# MIDI_CV_CONV.net
KiCad netlist of a schematic drawn in EAGLE
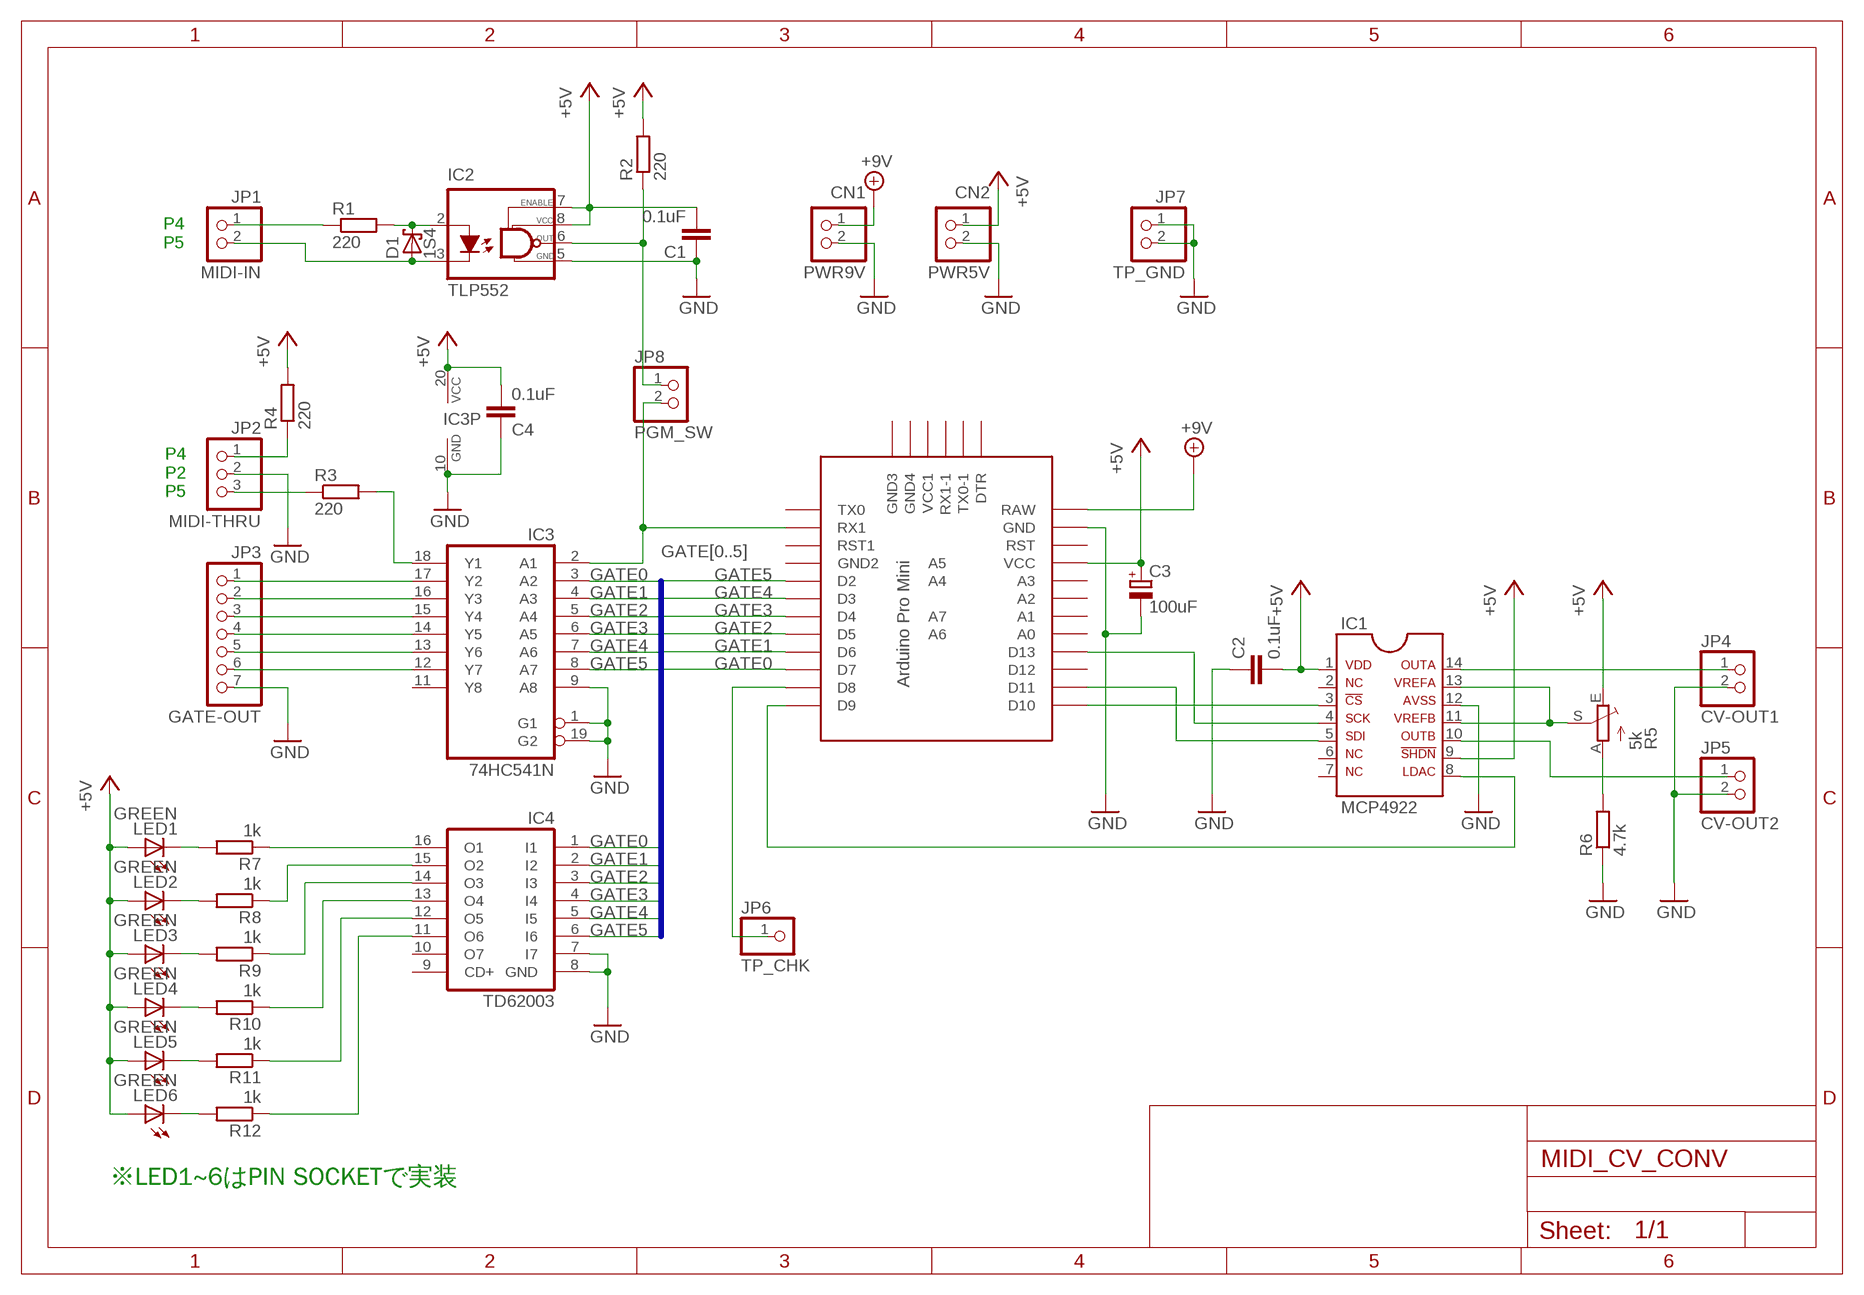
[diagram p0: schematic, sheet 1]

(export (version "E")
  (design (tool "Eeschema 10.0.6"))
  (components
    (comp (ref "C1")
      (value "0.1uF")
      (footprint "eagle-import:C025-024X044")
      (libsource (lib "eagle-import") (part "C-EU025-024X044"))
    )
    (comp (ref "C2")
      (value "0.1uF")
      (footprint "eagle-import:C050-024X044")
      (libsource (lib "eagle-import") (part "C-EU050-024X044"))
    )
    (comp (ref "C3")
      (value "100uF")
      (footprint "eagle-import:E2,5-7")
      (libsource (lib "eagle-import") (part "CPOL-EUE2.5-7"))
    )
    (comp (ref "C4")
      (value "0.1uF")
      (footprint "eagle-import:C025-024X044")
      (libsource (lib "eagle-import") (part "C-EU025-024X044"))
    )
    (comp (ref "CN1")
      (value "PWR9V")
      (footprint "eagle-import:B2B-XH-A")
      (libsource (lib "eagle-import") (part "B2B-XH-A"))
    )
    (comp (ref "CN2")
      (value "PWR5V")
      (footprint "eagle-import:B2B-XH-A")
      (libsource (lib "eagle-import") (part "B2B-XH-A"))
    )
    (comp (ref "D1")
      (value "1S4")
      (footprint "eagle-import:DO35-7")
      (libsource (lib "eagle-import") (part "SCHOTTKY-DIODEDO35-7"))
    )
    (comp (ref "IC1")
      (value "MCP4922")
      (footprint "eagle-import:MCP4922")
      (libsource (lib "eagle-import") (part "MCP4922"))
    )
    (comp (ref "IC2")
      (value "TLP552")
      (footprint "eagle-import:DIL8")
      (libsource (lib "eagle-import") (part "TLP552"))
    )
    (comp (ref "IC3")
      (value "74HC541N")
      (footprint "eagle-import:DIL20")
      (libsource (lib "eagle-import") (part "74541NHC"))
    )
    (comp (ref "IC4")
      (value "TD62003")
      (footprint "eagle-import:DIL16")
      (libsource (lib "eagle-import") (part "ULN2001AN"))
    )
    (comp (ref "JP1")
      (value "MIDI-IN")
      (footprint "eagle-import:1X02")
      (libsource (lib "eagle-import") (part "PINHD-1X2"))
    )
    (comp (ref "JP2")
      (value "MIDI-THRU")
      (footprint "eagle-import:1X03")
      (libsource (lib "eagle-import") (part "PINHD-1X3"))
    )
    (comp (ref "JP3")
      (value "GATE-OUT")
      (footprint "eagle-import:1X07")
      (libsource (lib "eagle-import") (part "PINHD-1X7"))
    )
    (comp (ref "JP4")
      (value "CV-OUT1")
      (footprint "eagle-import:1X02")
      (libsource (lib "eagle-import") (part "PINHD-1X2"))
    )
    (comp (ref "JP5")
      (value "CV-OUT2")
      (footprint "eagle-import:1X02")
      (libsource (lib "eagle-import") (part "PINHD-1X2"))
    )
    (comp (ref "JP6")
      (value "TP_CHK")
      (footprint "eagle-import:1X01")
      (libsource (lib "eagle-import") (part "PINHD-1X1"))
    )
    (comp (ref "JP7")
      (value "TP_GND")
      (footprint "eagle-import:1X02")
      (libsource (lib "eagle-import") (part "PINHD-1X2"))
    )
    (comp (ref "JP8")
      (value "PGM_SW")
      (footprint "eagle-import:1X02")
      (libsource (lib "eagle-import") (part "PINHD-1X2"))
    )
    (comp (ref "LED1")
      (value "GREEN")
      (footprint "eagle-import:LED3MM")
      (libsource (lib "eagle-import") (part "LED3MM"))
    )
    (comp (ref "LED2")
      (value "GREEN")
      (footprint "eagle-import:LED3MM")
      (libsource (lib "eagle-import") (part "LED3MM"))
    )
    (comp (ref "LED3")
      (value "GREEN")
      (footprint "eagle-import:LED3MM")
      (libsource (lib "eagle-import") (part "LED3MM"))
    )
    (comp (ref "LED4")
      (value "GREEN")
      (footprint "eagle-import:LED3MM")
      (libsource (lib "eagle-import") (part "LED3MM"))
    )
    (comp (ref "LED5")
      (value "GREEN")
      (footprint "eagle-import:LED3MM")
      (libsource (lib "eagle-import") (part "LED3MM"))
    )
    (comp (ref "LED6")
      (value "GREEN")
      (footprint "eagle-import:LED3MM")
      (libsource (lib "eagle-import") (part "LED3MM"))
    )
    (comp (ref "R1")
      (value "220")
      (footprint "eagle-import:0207_7")
      (libsource (lib "eagle-import") (part "R-EU_0207/7"))
    )
    (comp (ref "R2")
      (value "220")
      (footprint "eagle-import:0207_7")
      (libsource (lib "eagle-import") (part "R-EU_0207/7"))
    )
    (comp (ref "R3")
      (value "220")
      (footprint "eagle-import:0207_7")
      (libsource (lib "eagle-import") (part "R-EU_0207/7"))
    )
    (comp (ref "R4")
      (value "220")
      (footprint "eagle-import:0207_7")
      (libsource (lib "eagle-import") (part "R-EU_0207/7"))
    )
    (comp (ref "R5")
      (value "5k")
      (footprint "eagle-import:CT6")
      (libsource (lib "eagle-import") (part "TRIM_EU-CT6"))
    )
    (comp (ref "R6")
      (value "4.7k")
      (footprint "eagle-import:0207_7")
      (libsource (lib "eagle-import") (part "R-EU_0207/7"))
    )
    (comp (ref "R7")
      (value "1k")
      (footprint "eagle-import:0207_2V")
      (libsource (lib "eagle-import") (part "R-EU_0207/2V"))
    )
    (comp (ref "R8")
      (value "1k")
      (footprint "eagle-import:0207_2V")
      (libsource (lib "eagle-import") (part "R-EU_0207/2V"))
    )
    (comp (ref "R9")
      (value "1k")
      (footprint "eagle-import:0207_2V")
      (libsource (lib "eagle-import") (part "R-EU_0207/2V"))
    )
    (comp (ref "R10")
      (value "1k")
      (footprint "eagle-import:0207_2V")
      (libsource (lib "eagle-import") (part "R-EU_0207/2V"))
    )
    (comp (ref "R11")
      (value "1k")
      (footprint "eagle-import:0207_2V")
      (libsource (lib "eagle-import") (part "R-EU_0207/2V"))
    )
    (comp (ref "R12")
      (value "1k")
      (footprint "eagle-import:0207_2V")
      (libsource (lib "eagle-import") (part "R-EU_0207/2V"))
    )
    (comp (ref "U$1")
      (value "PRO-MINI-2 (16MHz/5V)")
      (footprint "eagle-import:PRO-MINI-2")
      (libsource (lib "eagle-import") (part "PRO-MINI-2"))
    )
  )
  (nets
    (net (code "1") (name "+5V") (class "Default")
      (node (ref "C1") (pin "2") (pinfunction "2_2") (pintype "passive"))
      (node (ref "C2") (pin "2") (pinfunction "2_2") (pintype "passive"))
      (node (ref "C3") (pin "+") (pinfunction "+_+") (pintype "passive"))
      (node (ref "C4") (pin "2") (pinfunction "2_2") (pintype "passive"))
      (node (ref "CN2") (pin "1") (pinfunction "1_1") (pintype "passive"))
      (node (ref "IC1") (pin "1") (pinfunction "1_1") (pintype "power_in"))
      (node (ref "IC1") (pin "9") (pinfunction "9_9") (pintype "input"))
      (node (ref "IC2") (pin "7") (pinfunction "EN_7") (pintype "input"))
      (node (ref "IC2") (pin "8") (pinfunction "VCC_8") (pintype "power_in"))
      (node (ref "IC3") (pin "20") (pinfunction "VCC_20") (pintype "power_in"))
      (node (ref "LED1") (pin "A") (pinfunction "A_A") (pintype "passive"))
      (node (ref "LED2") (pin "A") (pinfunction "A_A") (pintype "passive"))
      (node (ref "LED3") (pin "A") (pinfunction "A_A") (pintype "passive"))
      (node (ref "LED4") (pin "A") (pinfunction "A_A") (pintype "passive"))
      (node (ref "LED5") (pin "A") (pinfunction "A_A") (pintype "passive"))
      (node (ref "LED6") (pin "A") (pinfunction "A_A") (pintype "passive"))
      (node (ref "R2") (pin "2") (pinfunction "2_2") (pintype "passive"))
      (node (ref "R4") (pin "2") (pinfunction "2_2") (pintype "passive"))
      (node (ref "R5") (pin "E") (pinfunction "E_E") (pintype "passive"))
      (node (ref "U$1") (pin "VCC") (pinfunction "VCC_VCC") (pintype "bidirectional"))
    )
    (net (code "2") (name "+9V") (class "Default")
      (node (ref "CN1") (pin "1") (pinfunction "1_1") (pintype "passive"))
      (node (ref "U$1") (pin "RAW") (pinfunction "RAW_RAW") (pintype "bidirectional"))
    )
    (net (code "3") (name "/GATE0") (class "Default")
      (node (ref "IC3") (pin "3") (pinfunction "A2_3") (pintype "input"))
      (node (ref "IC4") (pin "1") (pinfunction "I1_1") (pintype "input"))
      (node (ref "U$1") (pin "D7") (pinfunction "D7_D7") (pintype "bidirectional"))
    )
    (net (code "4") (name "/GATE1") (class "Default")
      (node (ref "IC3") (pin "4") (pinfunction "A3_4") (pintype "input"))
      (node (ref "IC4") (pin "2") (pinfunction "I2_2") (pintype "input"))
      (node (ref "U$1") (pin "D6") (pinfunction "D6_D6") (pintype "bidirectional"))
    )
    (net (code "5") (name "/GATE2") (class "Default")
      (node (ref "IC3") (pin "5") (pinfunction "A4_5") (pintype "input"))
      (node (ref "IC4") (pin "3") (pinfunction "I3_3") (pintype "input"))
      (node (ref "U$1") (pin "D5") (pinfunction "D5_D5") (pintype "bidirectional"))
    )
    (net (code "6") (name "/GATE3") (class "Default")
      (node (ref "IC3") (pin "6") (pinfunction "A5_6") (pintype "input"))
      (node (ref "IC4") (pin "4") (pinfunction "I4_4") (pintype "input"))
      (node (ref "U$1") (pin "D4") (pinfunction "D4_D4") (pintype "bidirectional"))
    )
    (net (code "7") (name "/GATE4") (class "Default")
      (node (ref "IC3") (pin "7") (pinfunction "A6_7") (pintype "input"))
      (node (ref "IC4") (pin "5") (pinfunction "I5_5") (pintype "input"))
      (node (ref "U$1") (pin "D3") (pinfunction "D3_D3") (pintype "bidirectional"))
    )
    (net (code "8") (name "/GATE5") (class "Default")
      (node (ref "IC3") (pin "8") (pinfunction "A7_8") (pintype "input"))
      (node (ref "IC4") (pin "6") (pinfunction "I6_6") (pintype "input"))
      (node (ref "U$1") (pin "D2") (pinfunction "D2_D2") (pintype "bidirectional"))
    )
    (net (code "9") (name "GND") (class "Default")
      (node (ref "C1") (pin "1") (pinfunction "1_1") (pintype "passive"))
      (node (ref "C2") (pin "1") (pinfunction "1_1") (pintype "passive"))
      (node (ref "C3") (pin "-") (pinfunction "-_-") (pintype "passive"))
      (node (ref "C4") (pin "1") (pinfunction "1_1") (pintype "passive"))
      (node (ref "CN1") (pin "2") (pinfunction "2_2") (pintype "passive"))
      (node (ref "CN2") (pin "2") (pinfunction "2_2") (pintype "passive"))
      (node (ref "IC1") (pin "12") (pinfunction "12_12") (pintype "power_in"))
      (node (ref "IC2") (pin "5") (pinfunction "GND_5") (pintype "power_in"))
      (node (ref "IC3") (pin "1") (pinfunction "G1_1") (pintype "input"))
      (node (ref "IC3") (pin "10") (pinfunction "GND_10") (pintype "power_in"))
      (node (ref "IC3") (pin "19") (pinfunction "G2_19") (pintype "input"))
      (node (ref "IC3") (pin "9") (pinfunction "A8_9") (pintype "input"))
      (node (ref "IC4") (pin "7") (pinfunction "I7_7") (pintype "input"))
      (node (ref "IC4") (pin "8") (pinfunction "GND_8") (pintype "power_in"))
      (node (ref "JP2") (pin "2") (pinfunction "2_2") (pintype "passive"))
      (node (ref "JP3") (pin "7") (pinfunction "7_7") (pintype "passive"))
      (node (ref "JP4") (pin "2") (pinfunction "2_2") (pintype "passive"))
      (node (ref "JP5") (pin "2") (pinfunction "2_2") (pintype "passive"))
      (node (ref "JP7") (pin "1") (pinfunction "1_1") (pintype "passive"))
      (node (ref "JP7") (pin "2") (pinfunction "2_2") (pintype "passive"))
      (node (ref "R6") (pin "1") (pinfunction "1_1") (pintype "passive"))
      (node (ref "U$1") (pin "GND") (pinfunction "GND_GND") (pintype "bidirectional"))
    )
    (net (code "10") (name "Net-(IC1-Pad3)") (class "Default")
      (node (ref "IC1") (pin "3") (pinfunction "3_3") (pintype "input"))
      (node (ref "U$1") (pin "D10") (pinfunction "D10_D10") (pintype "bidirectional"))
    )
    (net (code "11") (name "Net-(IC1-Pad4)") (class "Default")
      (node (ref "IC1") (pin "4") (pinfunction "4_4") (pintype "input"))
      (node (ref "U$1") (pin "D13") (pinfunction "D13_D13") (pintype "bidirectional"))
    )
    (net (code "12") (name "Net-(IC1-Pad5)") (class "Default")
      (node (ref "IC1") (pin "5") (pinfunction "5_5") (pintype "input"))
      (node (ref "U$1") (pin "D11") (pinfunction "D11_D11") (pintype "bidirectional"))
    )
    (net (code "13") (name "Net-(IC1-Pad8)") (class "Default")
      (node (ref "IC1") (pin "8") (pinfunction "8_8") (pintype "input"))
      (node (ref "U$1") (pin "D9") (pinfunction "D9_D9") (pintype "bidirectional"))
    )
    (net (code "14") (name "Net-(IC1-Pad10)") (class "Default")
      (node (ref "IC1") (pin "10") (pinfunction "10_10") (pintype "output"))
      (node (ref "JP5") (pin "1") (pinfunction "1_1") (pintype "passive"))
    )
    (net (code "15") (name "Net-(IC1-Pad11)") (class "Default")
      (node (ref "IC1") (pin "11") (pinfunction "11_11") (pintype "input"))
      (node (ref "IC1") (pin "13") (pinfunction "13_13") (pintype "input"))
      (node (ref "R5") (pin "S") (pinfunction "S_S") (pintype "passive"))
    )
    (net (code "16") (name "Net-(IC1-Pad14)") (class "Default")
      (node (ref "IC1") (pin "14") (pinfunction "14_14") (pintype "output"))
      (node (ref "JP4") (pin "1") (pinfunction "1_1") (pintype "passive"))
    )
    (net (code "17") (name "Net-(IC2-A)") (class "Default")
      (node (ref "D1") (pin "C") (pinfunction "C_C") (pintype "passive"))
      (node (ref "IC2") (pin "2") (pinfunction "A_2") (pintype "passive"))
      (node (ref "R1") (pin "2") (pinfunction "2_2") (pintype "passive"))
    )
    (net (code "18") (name "Net-(IC2-C)") (class "Default")
      (node (ref "D1") (pin "A") (pinfunction "A_A") (pintype "passive"))
      (node (ref "IC2") (pin "3") (pinfunction "C_3") (pintype "passive"))
      (node (ref "JP1") (pin "2") (pinfunction "2_2") (pintype "passive"))
    )
    (net (code "19") (name "Net-(IC2-OUT)") (class "Default")
      (node (ref "IC2") (pin "6") (pinfunction "OUT_6") (pintype "output"))
      (node (ref "JP8") (pin "1") (pinfunction "1_1") (pintype "passive"))
      (node (ref "R2") (pin "1") (pinfunction "1_1") (pintype "passive"))
    )
    (net (code "20") (name "Net-(IC3A-A1)") (class "Default")
      (node (ref "IC3") (pin "2") (pinfunction "A1_2") (pintype "input"))
      (node (ref "JP8") (pin "2") (pinfunction "2_2") (pintype "passive"))
      (node (ref "U$1") (pin "RX1") (pinfunction "RX1_RX1") (pintype "bidirectional"))
    )
    (net (code "21") (name "Net-(IC3A-Y1)") (class "Default")
      (node (ref "IC3") (pin "18") (pinfunction "Y1_18") (pintype "tri_state"))
      (node (ref "R3") (pin "2") (pinfunction "2_2") (pintype "passive"))
    )
    (net (code "22") (name "Net-(IC3A-Y2)") (class "Default")
      (node (ref "IC3") (pin "17") (pinfunction "Y2_17") (pintype "tri_state"))
      (node (ref "JP3") (pin "1") (pinfunction "1_1") (pintype "passive"))
    )
    (net (code "23") (name "Net-(IC3A-Y3)") (class "Default")
      (node (ref "IC3") (pin "16") (pinfunction "Y3_16") (pintype "tri_state"))
      (node (ref "JP3") (pin "2") (pinfunction "2_2") (pintype "passive"))
    )
    (net (code "24") (name "Net-(IC3A-Y4)") (class "Default")
      (node (ref "IC3") (pin "15") (pinfunction "Y4_15") (pintype "tri_state"))
      (node (ref "JP3") (pin "3") (pinfunction "3_3") (pintype "passive"))
    )
    (net (code "25") (name "Net-(IC3A-Y5)") (class "Default")
      (node (ref "IC3") (pin "14") (pinfunction "Y5_14") (pintype "tri_state"))
      (node (ref "JP3") (pin "4") (pinfunction "4_4") (pintype "passive"))
    )
    (net (code "26") (name "Net-(IC3A-Y6)") (class "Default")
      (node (ref "IC3") (pin "13") (pinfunction "Y6_13") (pintype "tri_state"))
      (node (ref "JP3") (pin "5") (pinfunction "5_5") (pintype "passive"))
    )
    (net (code "27") (name "Net-(IC3A-Y7)") (class "Default")
      (node (ref "IC3") (pin "12") (pinfunction "Y7_12") (pintype "tri_state"))
      (node (ref "JP3") (pin "6") (pinfunction "6_6") (pintype "passive"))
    )
    (net (code "28") (name "Net-(IC4-O1)") (class "Default")
      (node (ref "IC4") (pin "16") (pinfunction "O1_16") (pintype "open_collector"))
      (node (ref "R7") (pin "1") (pinfunction "1_1") (pintype "passive"))
    )
    (net (code "29") (name "Net-(IC4-O2)") (class "Default")
      (node (ref "IC4") (pin "15") (pinfunction "O2_15") (pintype "open_collector"))
      (node (ref "R8") (pin "1") (pinfunction "1_1") (pintype "passive"))
    )
    (net (code "30") (name "Net-(IC4-O3)") (class "Default")
      (node (ref "IC4") (pin "14") (pinfunction "O3_14") (pintype "open_collector"))
      (node (ref "R9") (pin "1") (pinfunction "1_1") (pintype "passive"))
    )
    (net (code "31") (name "Net-(IC4-O4)") (class "Default")
      (node (ref "IC4") (pin "13") (pinfunction "O4_13") (pintype "open_collector"))
      (node (ref "R10") (pin "1") (pinfunction "1_1") (pintype "passive"))
    )
    (net (code "32") (name "Net-(IC4-O5)") (class "Default")
      (node (ref "IC4") (pin "12") (pinfunction "O5_12") (pintype "open_collector"))
      (node (ref "R11") (pin "1") (pinfunction "1_1") (pintype "passive"))
    )
    (net (code "33") (name "Net-(IC4-O6)") (class "Default")
      (node (ref "IC4") (pin "11") (pinfunction "O6_11") (pintype "open_collector"))
      (node (ref "R12") (pin "1") (pinfunction "1_1") (pintype "passive"))
    )
    (net (code "34") (name "Net-(JP1-Pad1)") (class "Default")
      (node (ref "JP1") (pin "1") (pinfunction "1_1") (pintype "passive"))
      (node (ref "R1") (pin "1") (pinfunction "1_1") (pintype "passive"))
    )
    (net (code "35") (name "Net-(JP2-Pad1)") (class "Default")
      (node (ref "JP2") (pin "1") (pinfunction "1_1") (pintype "passive"))
      (node (ref "R4") (pin "1") (pinfunction "1_1") (pintype "passive"))
    )
    (net (code "36") (name "Net-(JP2-Pad3)") (class "Default")
      (node (ref "JP2") (pin "3") (pinfunction "3_3") (pintype "passive"))
      (node (ref "R3") (pin "1") (pinfunction "1_1") (pintype "passive"))
    )
    (net (code "37") (name "Net-(JP6-Pad1)") (class "Default")
      (node (ref "JP6") (pin "1") (pinfunction "1_1") (pintype "passive"))
      (node (ref "U$1") (pin "D8") (pinfunction "D8_D8") (pintype "bidirectional"))
    )
    (net (code "38") (name "Net-(LED1-C)") (class "Default")
      (node (ref "LED1") (pin "K") (pinfunction "C_K") (pintype "passive"))
      (node (ref "R7") (pin "2") (pinfunction "2_2") (pintype "passive"))
    )
    (net (code "39") (name "Net-(LED2-C)") (class "Default")
      (node (ref "LED2") (pin "K") (pinfunction "C_K") (pintype "passive"))
      (node (ref "R8") (pin "2") (pinfunction "2_2") (pintype "passive"))
    )
    (net (code "40") (name "Net-(LED3-C)") (class "Default")
      (node (ref "LED3") (pin "K") (pinfunction "C_K") (pintype "passive"))
      (node (ref "R9") (pin "2") (pinfunction "2_2") (pintype "passive"))
    )
    (net (code "41") (name "Net-(LED4-C)") (class "Default")
      (node (ref "LED4") (pin "K") (pinfunction "C_K") (pintype "passive"))
      (node (ref "R10") (pin "2") (pinfunction "2_2") (pintype "passive"))
    )
    (net (code "42") (name "Net-(LED5-C)") (class "Default")
      (node (ref "LED5") (pin "K") (pinfunction "C_K") (pintype "passive"))
      (node (ref "R11") (pin "2") (pinfunction "2_2") (pintype "passive"))
    )
    (net (code "43") (name "Net-(LED6-C)") (class "Default")
      (node (ref "LED6") (pin "K") (pinfunction "C_K") (pintype "passive"))
      (node (ref "R12") (pin "2") (pinfunction "2_2") (pintype "passive"))
    )
    (net (code "44") (name "Net-(R5-PadA)") (class "Default")
      (node (ref "R5") (pin "A") (pinfunction "A_A") (pintype "passive"))
      (node (ref "R6") (pin "2") (pinfunction "2_2") (pintype "passive"))
    )
    (net (code "45") (name "unconnected-(IC1-Pad2)") (class "Default")
      (node (ref "IC1") (pin "2") (pinfunction "2_2") (pintype "no_connect"))
    )
    (net (code "46") (name "unconnected-(IC1-Pad6)") (class "Default")
      (node (ref "IC1") (pin "6") (pinfunction "6_6") (pintype "no_connect"))
    )
    (net (code "47") (name "unconnected-(IC1-Pad7)") (class "Default")
      (node (ref "IC1") (pin "7") (pinfunction "7_7") (pintype "no_connect"))
    )
    (net (code "48") (name "unconnected-(IC3A-Y8-Pad11)") (class "Default")
      (node (ref "IC3") (pin "11") (pinfunction "Y8_11") (pintype "tri_state"))
    )
    (net (code "49") (name "unconnected-(IC4-CD+-Pad9)") (class "Default")
      (node (ref "IC4") (pin "9") (pinfunction "CD+_9") (pintype "passive"))
    )
    (net (code "50") (name "unconnected-(IC4-O7-Pad10)") (class "Default")
      (node (ref "IC4") (pin "10") (pinfunction "O7_10") (pintype "open_collector"))
    )
    (net (code "51") (name "unconnected-(U$1-GND2-PadGND1)") (class "Default")
      (node (ref "U$1") (pin "GND1") (pinfunction "GND2_GND1") (pintype "bidirectional"))
    )
    (net (code "52") (name "unconnected-(U$1-GND3-PadGND2)") (class "Default")
      (node (ref "U$1") (pin "GND2") (pinfunction "GND3_GND2") (pintype "bidirectional"))
    )
    (net (code "53") (name "unconnected-(U$1-GND4-PadGND3)") (class "Default")
      (node (ref "U$1") (pin "GND3") (pinfunction "GND4_GND3") (pintype "bidirectional"))
    )
    (net (code "54") (name "unconnected-(U$1-PadA0)") (class "Default")
      (node (ref "U$1") (pin "A0") (pinfunction "A0_A0") (pintype "bidirectional"))
    )
    (net (code "55") (name "unconnected-(U$1-PadA1)") (class "Default")
      (node (ref "U$1") (pin "A1") (pinfunction "A1_A1") (pintype "bidirectional"))
    )
    (net (code "56") (name "unconnected-(U$1-PadA2)") (class "Default")
      (node (ref "U$1") (pin "A2") (pinfunction "A2_A2") (pintype "bidirectional"))
    )
    (net (code "57") (name "unconnected-(U$1-PadA3)") (class "Default")
      (node (ref "U$1") (pin "A3") (pinfunction "A3_A3") (pintype "bidirectional"))
    )
    (net (code "58") (name "unconnected-(U$1-PadA4)") (class "Default")
      (node (ref "U$1") (pin "A4") (pinfunction "A4_A4") (pintype "bidirectional"))
    )
    (net (code "59") (name "unconnected-(U$1-PadA5)") (class "Default")
      (node (ref "U$1") (pin "A5") (pinfunction "A5_A5") (pintype "bidirectional"))
    )
    (net (code "60") (name "unconnected-(U$1-PadA6)") (class "Default")
      (node (ref "U$1") (pin "A6") (pinfunction "A6_A6") (pintype "bidirectional"))
    )
    (net (code "61") (name "unconnected-(U$1-PadA7)") (class "Default")
      (node (ref "U$1") (pin "A7") (pinfunction "A7_A7") (pintype "bidirectional"))
    )
    (net (code "62") (name "unconnected-(U$1-PadD12)") (class "Default")
      (node (ref "U$1") (pin "D12") (pinfunction "D12_D12") (pintype "bidirectional"))
    )
    (net (code "63") (name "unconnected-(U$1-PadDTR)") (class "Default")
      (node (ref "U$1") (pin "DTR") (pinfunction "DTR_DTR") (pintype "bidirectional"))
    )
    (net (code "64") (name "unconnected-(U$1-PadRST)") (class "Default")
      (node (ref "U$1") (pin "RST") (pinfunction "RST_RST") (pintype "bidirectional"))
    )
    (net (code "65") (name "unconnected-(U$1-PadRST1)") (class "Default")
      (node (ref "U$1") (pin "RST1") (pinfunction "RST1_RST1") (pintype "bidirectional"))
    )
    (net (code "66") (name "unconnected-(U$1-PadRX1-1)") (class "Default")
      (node (ref "U$1") (pin "RX1-1") (pinfunction "RX1-1_RX1-1") (pintype "bidirectional"))
    )
    (net (code "67") (name "unconnected-(U$1-PadTX0)") (class "Default")
      (node (ref "U$1") (pin "TX0") (pinfunction "TX0_TX0") (pintype "bidirectional"))
    )
    (net (code "68") (name "unconnected-(U$1-PadTX0-1)") (class "Default")
      (node (ref "U$1") (pin "TX0-1") (pinfunction "TX0-1_TX0-1") (pintype "bidirectional"))
    )
    (net (code "69") (name "unconnected-(U$1-PadVCC1)") (class "Default")
      (node (ref "U$1") (pin "VCC1") (pinfunction "VCC1_VCC1") (pintype "bidirectional"))
    )
  )
)
